# 5x4-soundboard_arduino_pro_mini.net
KiCad netlist of a schematic drawn in EAGLE
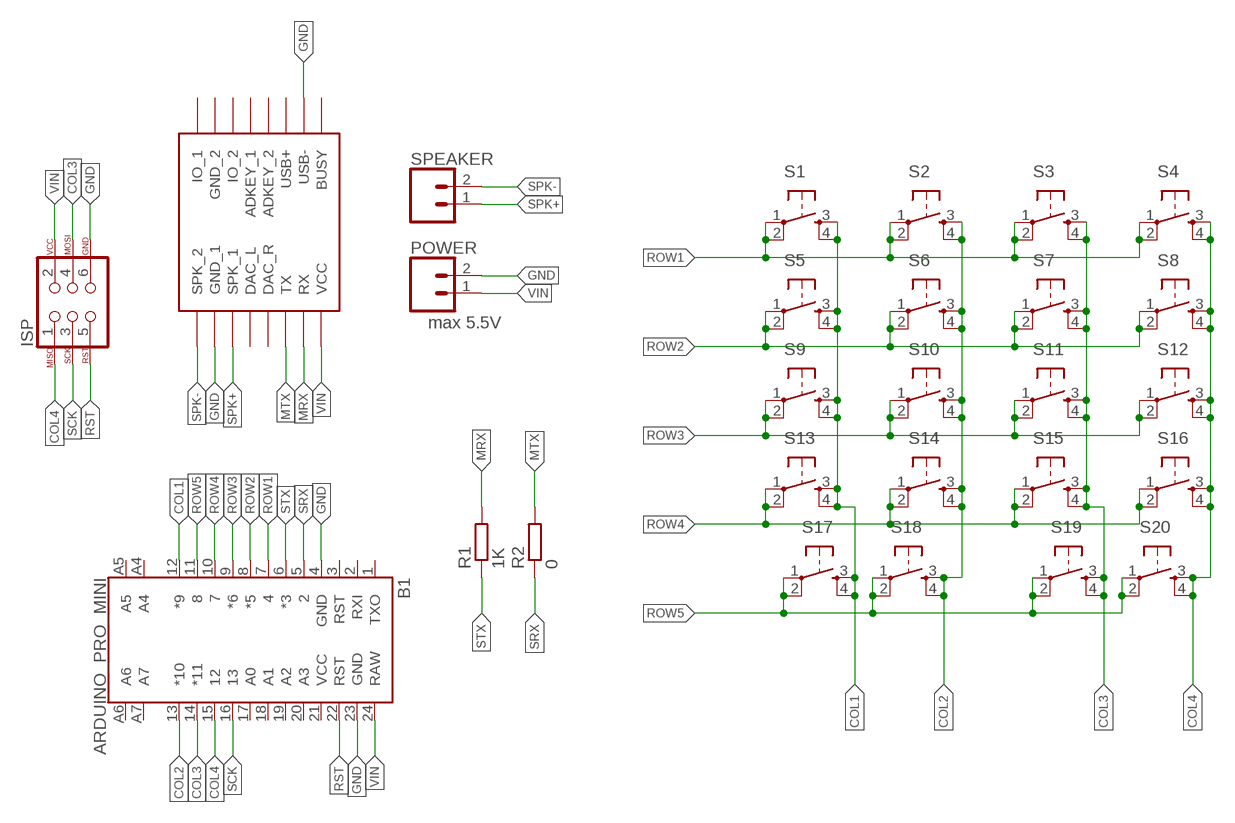
[diagram p0: schematic, sheet 1]

(export (version "E")
  (design (tool "Eeschema 10.0.6"))
  (components
    (comp (ref "B1")
      (value "ARDUINO_PRO_MINI")
      (footprint "eagle-import:ARDUINO_PRO_MINI")
      (libsource (lib "eagle-import") (part "ARDUINO_PRO_MINI"))
    )
    (comp (ref "ISP")
      (value "AVR_SPI_PROG_3X2PTH")
      (footprint "eagle-import:2X3")
      (libsource (lib "eagle-import") (part "AVR_SPI_PROG_3X2PTH"))
    )
    (comp (ref "POWER")
      (value "CONN_02LOCK_LONGPADS")
      (footprint "eagle-import:1X02_LOCK_LONGPADS")
      (libsource (lib "eagle-import") (part "CONN_02LOCK_LONGPADS"))
    )
    (comp (ref "R1")
      (value "1K")
      (footprint "eagle-import:0207_10")
      (libsource (lib "eagle-import") (part "R-EU_0207/10"))
    )
    (comp (ref "R2")
      (value "0")
      (footprint "eagle-import:0207_10")
      (libsource (lib "eagle-import") (part "R-EU_0207/10"))
    )
    (comp (ref "S1")
      (value "TAC_SWITCHPTH")
      (footprint "eagle-import:TACTILE-PTH")
      (libsource (lib "eagle-import") (part "TAC_SWITCHPTH"))
    )
    (comp (ref "S2")
      (value "TAC_SWITCHPTH")
      (footprint "eagle-import:TACTILE-PTH")
      (libsource (lib "eagle-import") (part "TAC_SWITCHPTH"))
    )
    (comp (ref "S3")
      (value "TAC_SWITCHPTH")
      (footprint "eagle-import:TACTILE-PTH")
      (libsource (lib "eagle-import") (part "TAC_SWITCHPTH"))
    )
    (comp (ref "S4")
      (value "TAC_SWITCHPTH")
      (footprint "eagle-import:TACTILE-PTH")
      (libsource (lib "eagle-import") (part "TAC_SWITCHPTH"))
    )
    (comp (ref "S5")
      (value "TAC_SWITCHPTH")
      (footprint "eagle-import:TACTILE-PTH")
      (libsource (lib "eagle-import") (part "TAC_SWITCHPTH"))
    )
    (comp (ref "S6")
      (value "TAC_SWITCHPTH")
      (footprint "eagle-import:TACTILE-PTH")
      (libsource (lib "eagle-import") (part "TAC_SWITCHPTH"))
    )
    (comp (ref "S7")
      (value "TAC_SWITCHPTH")
      (footprint "eagle-import:TACTILE-PTH")
      (libsource (lib "eagle-import") (part "TAC_SWITCHPTH"))
    )
    (comp (ref "S8")
      (value "TAC_SWITCHPTH")
      (footprint "eagle-import:TACTILE-PTH")
      (libsource (lib "eagle-import") (part "TAC_SWITCHPTH"))
    )
    (comp (ref "S9")
      (value "TAC_SWITCHPTH")
      (footprint "eagle-import:TACTILE-PTH")
      (libsource (lib "eagle-import") (part "TAC_SWITCHPTH"))
    )
    (comp (ref "S10")
      (value "TAC_SWITCHPTH")
      (footprint "eagle-import:TACTILE-PTH")
      (libsource (lib "eagle-import") (part "TAC_SWITCHPTH"))
    )
    (comp (ref "S11")
      (value "TAC_SWITCHPTH")
      (footprint "eagle-import:TACTILE-PTH")
      (libsource (lib "eagle-import") (part "TAC_SWITCHPTH"))
    )
    (comp (ref "S12")
      (value "TAC_SWITCHPTH")
      (footprint "eagle-import:TACTILE-PTH")
      (libsource (lib "eagle-import") (part "TAC_SWITCHPTH"))
    )
    (comp (ref "S13")
      (value "TAC_SWITCHPTH")
      (footprint "eagle-import:TACTILE-PTH")
      (libsource (lib "eagle-import") (part "TAC_SWITCHPTH"))
    )
    (comp (ref "S14")
      (value "TAC_SWITCHPTH")
      (footprint "eagle-import:TACTILE-PTH")
      (libsource (lib "eagle-import") (part "TAC_SWITCHPTH"))
    )
    (comp (ref "S15")
      (value "TAC_SWITCHPTH")
      (footprint "eagle-import:TACTILE-PTH")
      (libsource (lib "eagle-import") (part "TAC_SWITCHPTH"))
    )
    (comp (ref "S16")
      (value "TAC_SWITCHPTH")
      (footprint "eagle-import:TACTILE-PTH")
      (libsource (lib "eagle-import") (part "TAC_SWITCHPTH"))
    )
    (comp (ref "S17")
      (value "TAC_SWITCHPTH")
      (footprint "eagle-import:TACTILE-PTH")
      (libsource (lib "eagle-import") (part "TAC_SWITCHPTH"))
    )
    (comp (ref "S18")
      (value "TAC_SWITCHPTH")
      (footprint "eagle-import:TACTILE-PTH")
      (libsource (lib "eagle-import") (part "TAC_SWITCHPTH"))
    )
    (comp (ref "S19")
      (value "TAC_SWITCHPTH")
      (footprint "eagle-import:TACTILE-PTH")
      (libsource (lib "eagle-import") (part "TAC_SWITCHPTH"))
    )
    (comp (ref "S20")
      (value "TAC_SWITCHPTH")
      (footprint "eagle-import:TACTILE-PTH")
      (libsource (lib "eagle-import") (part "TAC_SWITCHPTH"))
    )
    (comp (ref "SPEAKER")
      (value "CONN_02LOCK_LONGPADS")
      (footprint "eagle-import:1X02_LOCK_LONGPADS")
      (libsource (lib "eagle-import") (part "CONN_02LOCK_LONGPADS"))
    )
    (comp (ref "U$1")
      (value "DFPLAYER")
      (footprint "eagle-import:DFPLAYER")
      (libsource (lib "eagle-import") (part "DFPLAYER"))
    )
  )
  (nets
    (net (code "1") (name "/VCC") (class "Default")
      (node (ref "B1") (pin "21") (pinfunction "VCC_21") (pintype "power_in"))
    )
    (net (code "2") (name "COL1") (class "Default")
      (node (ref "B1") (pin "12") (pinfunction "*9_12") (pintype "bidirectional"))
      (node (ref "S1") (pin "3") (pinfunction "3_3") (pintype "passive"))
      (node (ref "S1") (pin "4") (pinfunction "4_4") (pintype "passive"))
      (node (ref "S13") (pin "3") (pinfunction "3_3") (pintype "passive"))
      (node (ref "S13") (pin "4") (pinfunction "4_4") (pintype "passive"))
      (node (ref "S17") (pin "3") (pinfunction "3_3") (pintype "passive"))
      (node (ref "S17") (pin "4") (pinfunction "4_4") (pintype "passive"))
      (node (ref "S5") (pin "3") (pinfunction "3_3") (pintype "passive"))
      (node (ref "S5") (pin "4") (pinfunction "4_4") (pintype "passive"))
      (node (ref "S9") (pin "3") (pinfunction "3_3") (pintype "passive"))
      (node (ref "S9") (pin "4") (pinfunction "4_4") (pintype "passive"))
    )
    (net (code "3") (name "COL2") (class "Default")
      (node (ref "B1") (pin "13") (pinfunction "*10_13") (pintype "bidirectional"))
      (node (ref "S10") (pin "3") (pinfunction "3_3") (pintype "passive"))
      (node (ref "S10") (pin "4") (pinfunction "4_4") (pintype "passive"))
      (node (ref "S14") (pin "3") (pinfunction "3_3") (pintype "passive"))
      (node (ref "S14") (pin "4") (pinfunction "4_4") (pintype "passive"))
      (node (ref "S18") (pin "3") (pinfunction "3_3") (pintype "passive"))
      (node (ref "S18") (pin "4") (pinfunction "4_4") (pintype "passive"))
      (node (ref "S2") (pin "3") (pinfunction "3_3") (pintype "passive"))
      (node (ref "S2") (pin "4") (pinfunction "4_4") (pintype "passive"))
      (node (ref "S6") (pin "3") (pinfunction "3_3") (pintype "passive"))
      (node (ref "S6") (pin "4") (pinfunction "4_4") (pintype "passive"))
    )
    (net (code "4") (name "COL3") (class "Default")
      (node (ref "B1") (pin "14") (pinfunction "*11_14") (pintype "bidirectional"))
      (node (ref "ISP") (pin "4") (pinfunction "4_4") (pintype "passive"))
      (node (ref "S11") (pin "3") (pinfunction "3_3") (pintype "passive"))
      (node (ref "S11") (pin "4") (pinfunction "4_4") (pintype "passive"))
      (node (ref "S15") (pin "3") (pinfunction "3_3") (pintype "passive"))
      (node (ref "S15") (pin "4") (pinfunction "4_4") (pintype "passive"))
      (node (ref "S19") (pin "3") (pinfunction "3_3") (pintype "passive"))
      (node (ref "S19") (pin "4") (pinfunction "4_4") (pintype "passive"))
      (node (ref "S3") (pin "3") (pinfunction "3_3") (pintype "passive"))
      (node (ref "S3") (pin "4") (pinfunction "4_4") (pintype "passive"))
      (node (ref "S7") (pin "3") (pinfunction "3_3") (pintype "passive"))
      (node (ref "S7") (pin "4") (pinfunction "4_4") (pintype "passive"))
    )
    (net (code "5") (name "COL4") (class "Default")
      (node (ref "B1") (pin "15") (pinfunction "12_15") (pintype "bidirectional"))
      (node (ref "ISP") (pin "1") (pinfunction "1_1") (pintype "passive"))
      (node (ref "S12") (pin "3") (pinfunction "3_3") (pintype "passive"))
      (node (ref "S12") (pin "4") (pinfunction "4_4") (pintype "passive"))
      (node (ref "S16") (pin "3") (pinfunction "3_3") (pintype "passive"))
      (node (ref "S16") (pin "4") (pinfunction "4_4") (pintype "passive"))
      (node (ref "S20") (pin "3") (pinfunction "3_3") (pintype "passive"))
      (node (ref "S20") (pin "4") (pinfunction "4_4") (pintype "passive"))
      (node (ref "S4") (pin "3") (pinfunction "3_3") (pintype "passive"))
      (node (ref "S4") (pin "4") (pinfunction "4_4") (pintype "passive"))
      (node (ref "S8") (pin "3") (pinfunction "3_3") (pintype "passive"))
      (node (ref "S8") (pin "4") (pinfunction "4_4") (pintype "passive"))
    )
    (net (code "6") (name "GND") (class "Default")
      (node (ref "B1") (pin "23") (pinfunction "GND_23") (pintype "power_in"))
      (node (ref "B1") (pin "4") (pinfunction "GND_4") (pintype "power_in"))
      (node (ref "ISP") (pin "6") (pinfunction "6_6") (pintype "passive"))
      (node (ref "POWER") (pin "2") (pinfunction "2_2") (pintype "passive"))
      (node (ref "U$1") (pin "GND_1") (pinfunction "GND_1_GND_1") (pintype "bidirectional"))
      (node (ref "U$1") (pin "USB-") (pinfunction "USB-_USB-") (pintype "bidirectional"))
    )
    (net (code "7") (name "MRX") (class "Default")
      (node (ref "R1") (pin "2") (pinfunction "2_2") (pintype "passive"))
      (node (ref "U$1") (pin "RX") (pinfunction "RX_RX") (pintype "bidirectional"))
    )
    (net (code "8") (name "MTX") (class "Default")
      (node (ref "R2") (pin "2") (pinfunction "2_2") (pintype "passive"))
      (node (ref "U$1") (pin "TX") (pinfunction "TX_TX") (pintype "bidirectional"))
    )
    (net (code "9") (name "ROW1") (class "Default")
      (node (ref "B1") (pin "7") (pinfunction "4_7") (pintype "bidirectional"))
      (node (ref "S1") (pin "1") (pinfunction "1_1") (pintype "passive"))
      (node (ref "S1") (pin "2") (pinfunction "2_2") (pintype "passive"))
      (node (ref "S2") (pin "1") (pinfunction "1_1") (pintype "passive"))
      (node (ref "S2") (pin "2") (pinfunction "2_2") (pintype "passive"))
      (node (ref "S3") (pin "1") (pinfunction "1_1") (pintype "passive"))
      (node (ref "S3") (pin "2") (pinfunction "2_2") (pintype "passive"))
      (node (ref "S4") (pin "1") (pinfunction "1_1") (pintype "passive"))
      (node (ref "S4") (pin "2") (pinfunction "2_2") (pintype "passive"))
    )
    (net (code "10") (name "ROW2") (class "Default")
      (node (ref "B1") (pin "8") (pinfunction "*5_8") (pintype "bidirectional"))
      (node (ref "S5") (pin "1") (pinfunction "1_1") (pintype "passive"))
      (node (ref "S5") (pin "2") (pinfunction "2_2") (pintype "passive"))
      (node (ref "S6") (pin "1") (pinfunction "1_1") (pintype "passive"))
      (node (ref "S6") (pin "2") (pinfunction "2_2") (pintype "passive"))
      (node (ref "S7") (pin "1") (pinfunction "1_1") (pintype "passive"))
      (node (ref "S7") (pin "2") (pinfunction "2_2") (pintype "passive"))
      (node (ref "S8") (pin "1") (pinfunction "1_1") (pintype "passive"))
      (node (ref "S8") (pin "2") (pinfunction "2_2") (pintype "passive"))
    )
    (net (code "11") (name "ROW3") (class "Default")
      (node (ref "B1") (pin "9") (pinfunction "*6_9") (pintype "bidirectional"))
      (node (ref "S10") (pin "1") (pinfunction "1_1") (pintype "passive"))
      (node (ref "S10") (pin "2") (pinfunction "2_2") (pintype "passive"))
      (node (ref "S11") (pin "1") (pinfunction "1_1") (pintype "passive"))
      (node (ref "S11") (pin "2") (pinfunction "2_2") (pintype "passive"))
      (node (ref "S12") (pin "1") (pinfunction "1_1") (pintype "passive"))
      (node (ref "S12") (pin "2") (pinfunction "2_2") (pintype "passive"))
      (node (ref "S9") (pin "1") (pinfunction "1_1") (pintype "passive"))
      (node (ref "S9") (pin "2") (pinfunction "2_2") (pintype "passive"))
    )
    (net (code "12") (name "ROW4") (class "Default")
      (node (ref "B1") (pin "10") (pinfunction "7_10") (pintype "bidirectional"))
      (node (ref "S13") (pin "1") (pinfunction "1_1") (pintype "passive"))
      (node (ref "S13") (pin "2") (pinfunction "2_2") (pintype "passive"))
      (node (ref "S14") (pin "1") (pinfunction "1_1") (pintype "passive"))
      (node (ref "S14") (pin "2") (pinfunction "2_2") (pintype "passive"))
      (node (ref "S15") (pin "1") (pinfunction "1_1") (pintype "passive"))
      (node (ref "S15") (pin "2") (pinfunction "2_2") (pintype "passive"))
      (node (ref "S16") (pin "1") (pinfunction "1_1") (pintype "passive"))
      (node (ref "S16") (pin "2") (pinfunction "2_2") (pintype "passive"))
    )
    (net (code "13") (name "ROW5") (class "Default")
      (node (ref "B1") (pin "11") (pinfunction "8_11") (pintype "bidirectional"))
      (node (ref "S17") (pin "1") (pinfunction "1_1") (pintype "passive"))
      (node (ref "S17") (pin "2") (pinfunction "2_2") (pintype "passive"))
      (node (ref "S18") (pin "1") (pinfunction "1_1") (pintype "passive"))
      (node (ref "S18") (pin "2") (pinfunction "2_2") (pintype "passive"))
      (node (ref "S19") (pin "1") (pinfunction "1_1") (pintype "passive"))
      (node (ref "S19") (pin "2") (pinfunction "2_2") (pintype "passive"))
      (node (ref "S20") (pin "1") (pinfunction "1_1") (pintype "passive"))
      (node (ref "S20") (pin "2") (pinfunction "2_2") (pintype "passive"))
    )
    (net (code "14") (name "RST") (class "Default")
      (node (ref "B1") (pin "22") (pinfunction "RST_22") (pintype "bidirectional"))
      (node (ref "ISP") (pin "5") (pinfunction "5_5") (pintype "passive"))
    )
    (net (code "15") (name "SCK") (class "Default")
      (node (ref "B1") (pin "16") (pinfunction "13_16") (pintype "bidirectional"))
      (node (ref "ISP") (pin "3") (pinfunction "3_3") (pintype "passive"))
    )
    (net (code "16") (name "SPK+") (class "Default")
      (node (ref "SPEAKER") (pin "1") (pinfunction "1_1") (pintype "passive"))
      (node (ref "U$1") (pin "SPK1") (pinfunction "SPK_1_SPK1") (pintype "bidirectional"))
    )
    (net (code "17") (name "SPK-") (class "Default")
      (node (ref "SPEAKER") (pin "2") (pinfunction "2_2") (pintype "passive"))
      (node (ref "U$1") (pin "SPK2") (pinfunction "SPK_2_SPK2") (pintype "bidirectional"))
    )
    (net (code "18") (name "SRX") (class "Default")
      (node (ref "B1") (pin "5") (pinfunction "2_5") (pintype "bidirectional"))
      (node (ref "R2") (pin "1") (pinfunction "1_1") (pintype "passive"))
    )
    (net (code "19") (name "STX") (class "Default")
      (node (ref "B1") (pin "6") (pinfunction "*3_6") (pintype "bidirectional"))
      (node (ref "R1") (pin "1") (pinfunction "1_1") (pintype "passive"))
    )
    (net (code "20") (name "VIN") (class "Default")
      (node (ref "B1") (pin "24") (pinfunction "RAW_24") (pintype "power_in"))
      (node (ref "ISP") (pin "2") (pinfunction "2_2") (pintype "passive"))
      (node (ref "POWER") (pin "1") (pinfunction "1_1") (pintype "passive"))
      (node (ref "U$1") (pin "VCC") (pinfunction "VCC_VCC") (pintype "bidirectional"))
    )
    (net (code "21") (name "unconnected-(B1-A0-Pad17)") (class "Default")
      (node (ref "B1") (pin "17") (pinfunction "A0_17") (pintype "bidirectional"))
    )
    (net (code "22") (name "unconnected-(B1-A1-Pad18)") (class "Default")
      (node (ref "B1") (pin "18") (pinfunction "A1_18") (pintype "bidirectional"))
    )
    (net (code "23") (name "unconnected-(B1-A2-Pad19)") (class "Default")
      (node (ref "B1") (pin "19") (pinfunction "A2_19") (pintype "bidirectional"))
    )
    (net (code "24") (name "unconnected-(B1-A3-Pad20)") (class "Default")
      (node (ref "B1") (pin "20") (pinfunction "A3_20") (pintype "bidirectional"))
    )
    (net (code "25") (name "unconnected-(B1-PadA4)") (class "Default")
      (node (ref "B1") (pin "A4") (pinfunction "A4_A4") (pintype "bidirectional"))
    )
    (net (code "26") (name "unconnected-(B1-PadA5)") (class "Default")
      (node (ref "B1") (pin "A5") (pinfunction "A5_A5") (pintype "bidirectional"))
    )
    (net (code "27") (name "unconnected-(B1-PadA6)") (class "Default")
      (node (ref "B1") (pin "A6") (pinfunction "A6_A6") (pintype "bidirectional"))
    )
    (net (code "28") (name "unconnected-(B1-PadA7)") (class "Default")
      (node (ref "B1") (pin "A7") (pinfunction "A7_A7") (pintype "bidirectional"))
    )
    (net (code "29") (name "unconnected-(B1-RST-Pad3)") (class "Default")
      (node (ref "B1") (pin "3") (pinfunction "RST_3") (pintype "bidirectional"))
    )
    (net (code "30") (name "unconnected-(B1-RXI-Pad2)") (class "Default")
      (node (ref "B1") (pin "2") (pinfunction "RXI_2") (pintype "bidirectional"))
    )
    (net (code "31") (name "unconnected-(B1-TXO-Pad1)") (class "Default")
      (node (ref "B1") (pin "1") (pinfunction "TXO_1") (pintype "bidirectional"))
    )
    (net (code "32") (name "unconnected-(U$1-ADKEY_1-PadADKEY1)") (class "Default")
      (node (ref "U$1") (pin "ADKEY1") (pinfunction "ADKEY_1_ADKEY1") (pintype "bidirectional"))
    )
    (net (code "33") (name "unconnected-(U$1-ADKEY_2-PadADKEY2)") (class "Default")
      (node (ref "U$1") (pin "ADKEY2") (pinfunction "ADKEY_2_ADKEY2") (pintype "bidirectional"))
    )
    (net (code "34") (name "unconnected-(U$1-IO_1-PadIO1)") (class "Default")
      (node (ref "U$1") (pin "IO1") (pinfunction "IO_1_IO1") (pintype "bidirectional"))
    )
    (net (code "35") (name "unconnected-(U$1-IO_2-PadIO2)") (class "Default")
      (node (ref "U$1") (pin "IO2") (pinfunction "IO_2_IO2") (pintype "bidirectional"))
    )
    (net (code "36") (name "unconnected-(U$1-PadBUSY)") (class "Default")
      (node (ref "U$1") (pin "BUSY") (pinfunction "BUSY_BUSY") (pintype "bidirectional"))
    )
    (net (code "37") (name "unconnected-(U$1-PadDAC_L)") (class "Default")
      (node (ref "U$1") (pin "DAC_L") (pinfunction "DAC_L_DAC_L") (pintype "bidirectional"))
    )
    (net (code "38") (name "unconnected-(U$1-PadDAC_R)") (class "Default")
      (node (ref "U$1") (pin "DAC_R") (pinfunction "DAC_R_DAC_R") (pintype "bidirectional"))
    )
    (net (code "39") (name "unconnected-(U$1-PadGND_2)") (class "Default")
      (node (ref "U$1") (pin "GND_2") (pinfunction "GND_2_GND_2") (pintype "bidirectional"))
    )
    (net (code "40") (name "unconnected-(U$1-PadUSB+)") (class "Default")
      (node (ref "U$1") (pin "USB+") (pinfunction "USB+_USB+") (pintype "bidirectional"))
    )
  )
)
